# SoundDetectorModule.net
KiCad netlist of a schematic drawn in EAGLE
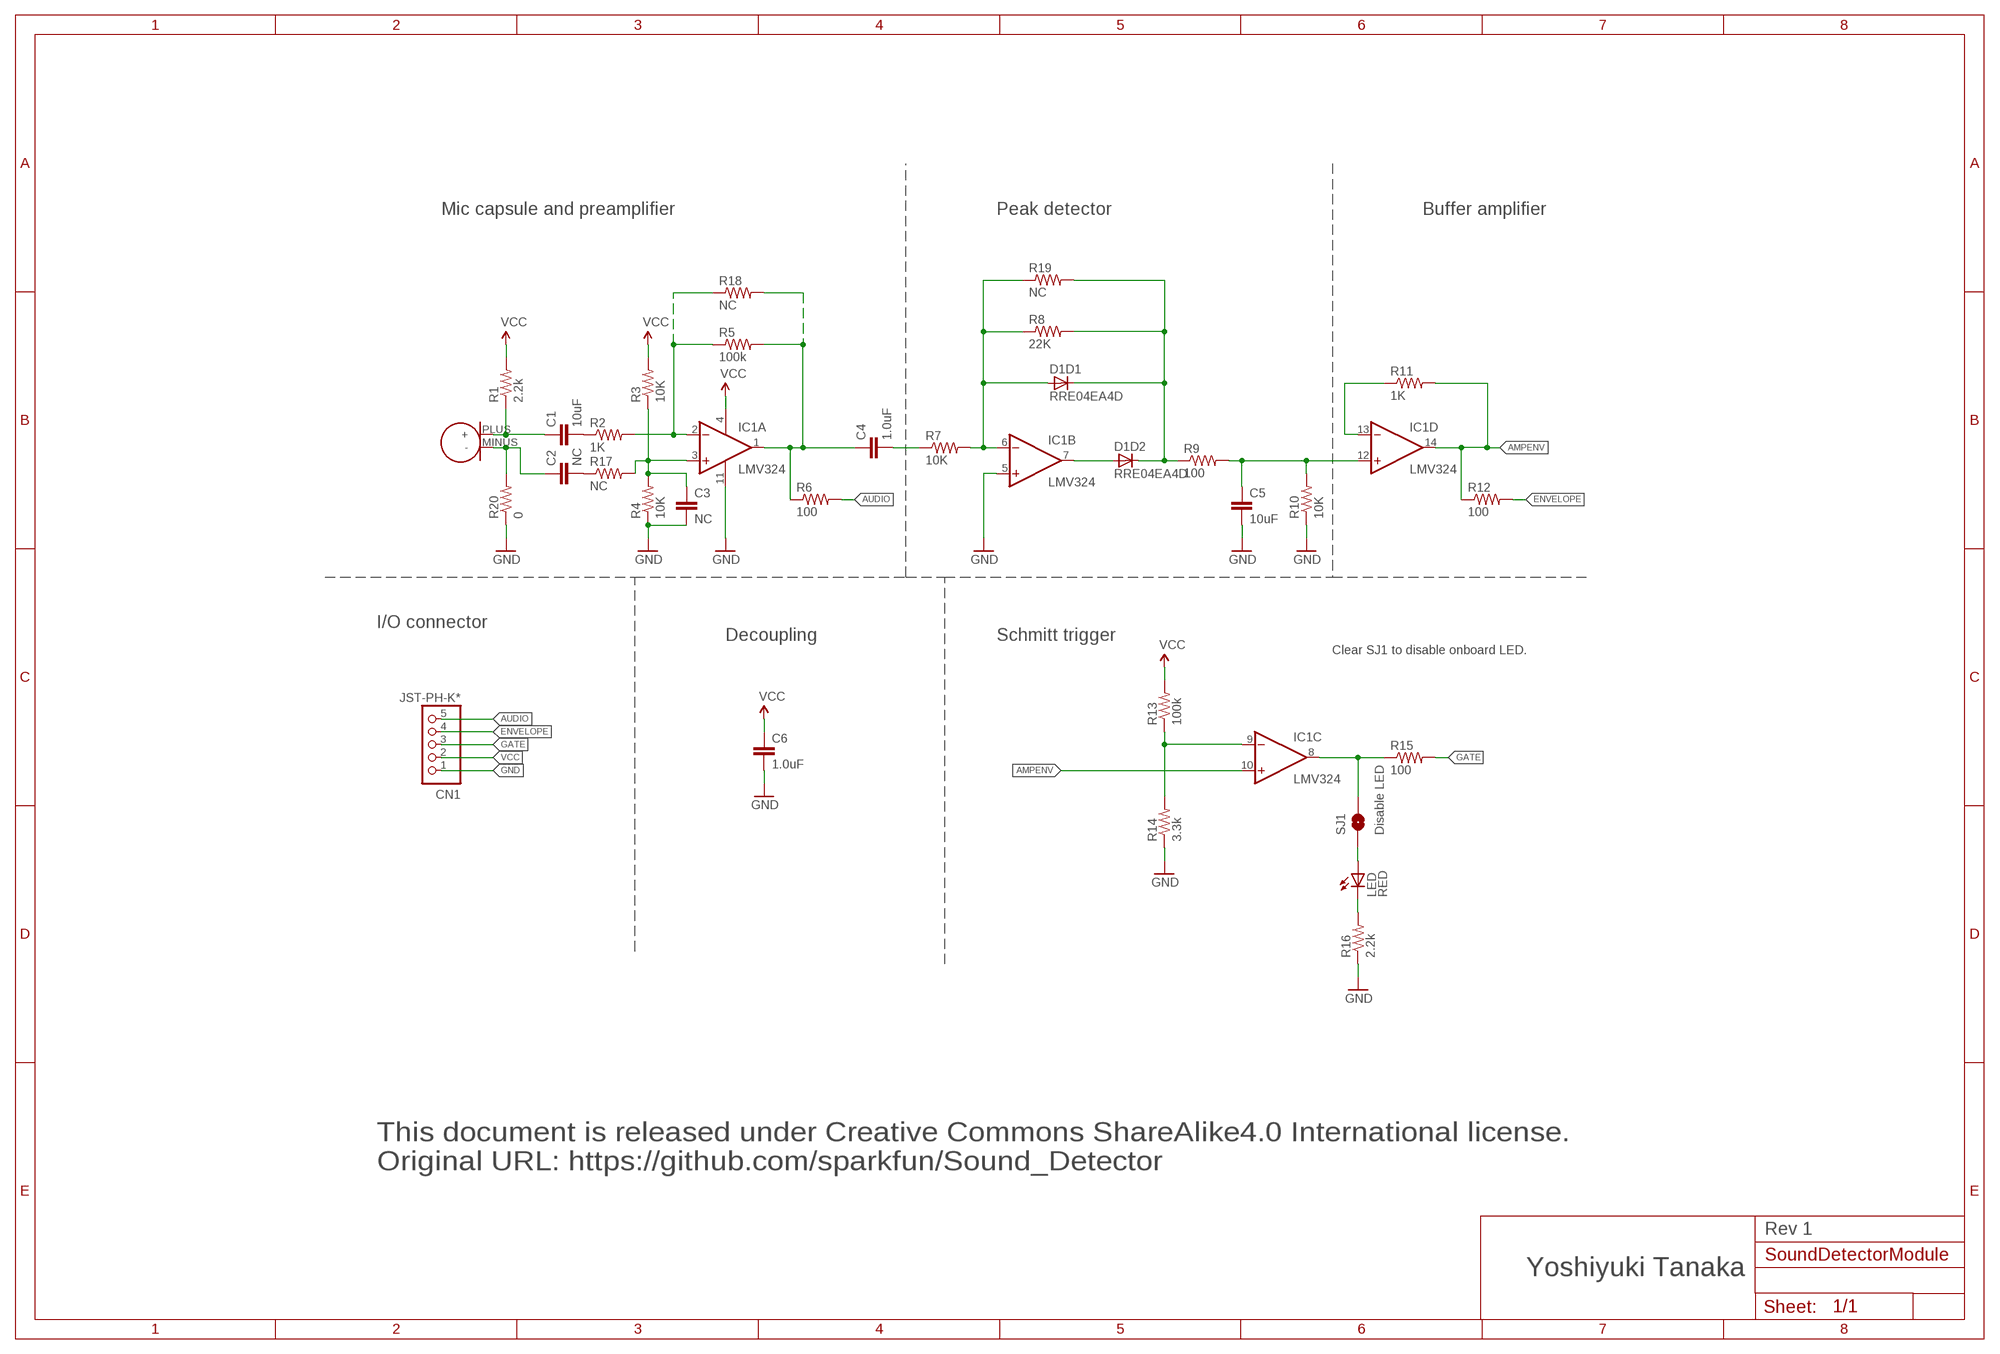
[diagram p0: schematic, sheet 1]

(export (version "E")
  (design (tool "Eeschema 10.0.6"))
  (components
    (comp (ref "A1")
      (value "MO093803-3")
      (footprint "eagle-import:MO093803-3")
      (libsource (lib "eagle-import") (part "MO093803-3"))
    )
    (comp (ref "C1")
      (value "10uF")
      (footprint "eagle-import:C1206")
      (libsource (lib "eagle-import") (part "C-EUC1206"))
    )
    (comp (ref "C2")
      (value "NC")
      (footprint "eagle-import:C0603")
      (libsource (lib "eagle-import") (part "C-EUC0603"))
    )
    (comp (ref "C3")
      (value "NC")
      (footprint "eagle-import:C0603")
      (libsource (lib "eagle-import") (part "C-EUC0603"))
    )
    (comp (ref "C4")
      (value "1.0uF")
      (footprint "eagle-import:C0603")
      (libsource (lib "eagle-import") (part "C-EUC0603"))
    )
    (comp (ref "C5")
      (value "10uF")
      (footprint "eagle-import:C1206")
      (libsource (lib "eagle-import") (part "C-EUC1206"))
    )
    (comp (ref "C6")
      (value "1.0uF")
      (footprint "eagle-import:C0603")
      (libsource (lib "eagle-import") (part "C-EUC0603"))
    )
    (comp (ref "CN1")
      (value "JST-PH-K*")
      (footprint "eagle-import:B5B-PH-SM4-TB")
      (libsource (lib "eagle-import") (part "B5B-PH-SM4-TB"))
    )
    (comp (ref "D1")
      (value "RRE04EA4D")
      (footprint "eagle-import:TSMD5")
      (libsource (lib "eagle-import") (part "RRE04EA4D"))
    )
    (comp (ref "IC1")
      (value "LMV324")
      (footprint "eagle-import:SO14")
      (libsource (lib "eagle-import") (part "LMV324"))
    )
    (comp (ref "LED")
      (value "RED")
      (footprint "eagle-import:SML-E1X")
      (libsource (lib "eagle-import") (part "SML-E1X"))
    )
    (comp (ref "R1")
      (value "2.2k")
      (footprint "eagle-import:R0603")
      (libsource (lib "eagle-import") (part "R-US_R0603"))
    )
    (comp (ref "R2")
      (value "1K")
      (footprint "eagle-import:R0603")
      (libsource (lib "eagle-import") (part "R-US_R0603"))
    )
    (comp (ref "R3")
      (value "10K")
      (footprint "eagle-import:R0603")
      (libsource (lib "eagle-import") (part "R-US_R0603"))
    )
    (comp (ref "R4")
      (value "10K")
      (footprint "eagle-import:R0603")
      (libsource (lib "eagle-import") (part "R-US_R0603"))
    )
    (comp (ref "R5")
      (value "100k")
      (footprint "eagle-import:R0603")
      (libsource (lib "eagle-import") (part "R-US_R0603"))
    )
    (comp (ref "R6")
      (value "100")
      (footprint "eagle-import:R0603")
      (libsource (lib "eagle-import") (part "R-US_R0603"))
    )
    (comp (ref "R7")
      (value "10K")
      (footprint "eagle-import:R0603")
      (libsource (lib "eagle-import") (part "R-US_R0603"))
    )
    (comp (ref "R8")
      (value "22K")
      (footprint "eagle-import:R0603")
      (libsource (lib "eagle-import") (part "R-US_R0603"))
    )
    (comp (ref "R9")
      (value "100")
      (footprint "eagle-import:R0603")
      (libsource (lib "eagle-import") (part "R-US_R0603"))
    )
    (comp (ref "R10")
      (value "10K")
      (footprint "eagle-import:R0603")
      (libsource (lib "eagle-import") (part "R-US_R0603"))
    )
    (comp (ref "R11")
      (value "1K")
      (footprint "eagle-import:R0603")
      (libsource (lib "eagle-import") (part "R-US_R0603"))
    )
    (comp (ref "R12")
      (value "100")
      (footprint "eagle-import:R0603")
      (libsource (lib "eagle-import") (part "R-US_R0603"))
    )
    (comp (ref "R13")
      (value "100k")
      (footprint "eagle-import:R0603")
      (libsource (lib "eagle-import") (part "R-US_R0603"))
    )
    (comp (ref "R14")
      (value "3.3k")
      (footprint "eagle-import:R0603")
      (libsource (lib "eagle-import") (part "R-US_R0603"))
    )
    (comp (ref "R15")
      (value "100")
      (footprint "eagle-import:R0603")
      (libsource (lib "eagle-import") (part "R-US_R0603"))
    )
    (comp (ref "R16")
      (value "2.2k")
      (footprint "eagle-import:R0603")
      (libsource (lib "eagle-import") (part "R-US_R0603"))
    )
    (comp (ref "R17")
      (value "NC")
      (footprint "eagle-import:R0603")
      (libsource (lib "eagle-import") (part "R-US_R0603"))
    )
    (comp (ref "R18")
      (value "NC")
      (footprint "eagle-import:0207_7")
      (libsource (lib "eagle-import") (part "resistor_R-US_0207/7"))
    )
    (comp (ref "R19")
      (value "NC")
      (footprint "eagle-import:0207_7")
      (libsource (lib "eagle-import") (part "resistor_R-US_0207/7"))
    )
    (comp (ref "R20")
      (value "0")
      (footprint "eagle-import:R0603")
      (libsource (lib "eagle-import") (part "R-US_R0603"))
    )
    (comp (ref "SJ1")
      (value "Disable LED")
      (footprint "eagle-import:SJ_2S")
      (libsource (lib "eagle-import") (part "SOLDERJUMPERNC"))
    )
  )
  (nets
    (net (code "1") (name "AMPENV") (class "Default")
      (node (ref "IC1") (pin "10") (pinfunction "+IN_10") (pintype "input"))
      (node (ref "IC1") (pin "14") (pinfunction "OUT_14") (pintype "output"))
      (node (ref "R11") (pin "2") (pinfunction "2_2") (pintype "passive"))
      (node (ref "R12") (pin "1") (pinfunction "1_1") (pintype "passive"))
    )
    (net (code "2") (name "AUDIO") (class "Default")
      (node (ref "CN1") (pin "5") (pinfunction "5_5") (pintype "passive"))
      (node (ref "R6") (pin "2") (pinfunction "2_2") (pintype "passive"))
    )
    (net (code "3") (name "ENVELOPE") (class "Default")
      (node (ref "CN1") (pin "4") (pinfunction "4_4") (pintype "passive"))
      (node (ref "R12") (pin "2") (pinfunction "2_2") (pintype "passive"))
    )
    (net (code "4") (name "GATE") (class "Default")
      (node (ref "CN1") (pin "3") (pinfunction "3_3") (pintype "passive"))
      (node (ref "R15") (pin "2") (pinfunction "2_2") (pintype "passive"))
    )
    (net (code "5") (name "GND") (class "Default")
      (node (ref "C3") (pin "2") (pinfunction "2_2") (pintype "passive"))
      (node (ref "C5") (pin "2") (pinfunction "2_2") (pintype "passive"))
      (node (ref "C6") (pin "2") (pinfunction "2_2") (pintype "passive"))
      (node (ref "CN1") (pin "1") (pinfunction "1_1") (pintype "passive"))
      (node (ref "IC1") (pin "11") (pinfunction "V-_11") (pintype "power_in"))
      (node (ref "IC1") (pin "5") (pinfunction "+IN_5") (pintype "input"))
      (node (ref "R10") (pin "1") (pinfunction "1_1") (pintype "passive"))
      (node (ref "R14") (pin "1") (pinfunction "1_1") (pintype "passive"))
      (node (ref "R16") (pin "1") (pinfunction "1_1") (pintype "passive"))
      (node (ref "R20") (pin "1") (pinfunction "1_1") (pintype "passive"))
      (node (ref "R4") (pin "1") (pinfunction "1_1") (pintype "passive"))
    )
    (net (code "6") (name "Net-(A1-+)") (class "Default")
      (node (ref "A1") (pin "PLUS") (pinfunction "+_PLUS") (pintype "bidirectional"))
      (node (ref "C1") (pin "1") (pinfunction "1_1") (pintype "passive"))
      (node (ref "R1") (pin "1") (pinfunction "1_1") (pintype "passive"))
    )
    (net (code "7") (name "Net-(A1--)") (class "Default")
      (node (ref "A1") (pin "MINUS") (pinfunction "-_MINUS") (pintype "bidirectional"))
      (node (ref "C2") (pin "1") (pinfunction "1_1") (pintype "passive"))
      (node (ref "R20") (pin "2") (pinfunction "2_2") (pintype "passive"))
    )
    (net (code "8") (name "Net-(C1-Pad2)") (class "Default")
      (node (ref "C1") (pin "2") (pinfunction "2_2") (pintype "passive"))
      (node (ref "R2") (pin "1") (pinfunction "1_1") (pintype "passive"))
    )
    (net (code "9") (name "Net-(C2-Pad2)") (class "Default")
      (node (ref "C2") (pin "2") (pinfunction "2_2") (pintype "passive"))
      (node (ref "R17") (pin "1") (pinfunction "1_1") (pintype "passive"))
    )
    (net (code "10") (name "Net-(C4-Pad2)") (class "Default")
      (node (ref "C4") (pin "2") (pinfunction "2_2") (pintype "passive"))
      (node (ref "R7") (pin "1") (pinfunction "1_1") (pintype "passive"))
    )
    (net (code "11") (name "Net-(D1A-A)") (class "Default")
      (node (ref "D1") (pin "1") (pinfunction "A_1") (pintype "passive"))
      (node (ref "IC1") (pin "6") (pinfunction "-IN_6") (pintype "input"))
      (node (ref "R19") (pin "1") (pinfunction "1_1") (pintype "passive"))
      (node (ref "R7") (pin "2") (pinfunction "2_2") (pintype "passive"))
      (node (ref "R8") (pin "1") (pinfunction "1_1") (pintype "passive"))
    )
    (net (code "12") (name "Net-(D1A-C)") (class "Default")
      (node (ref "D1") (pin "4") (pinfunction "C_4") (pintype "passive"))
      (node (ref "D1") (pin "5") (pinfunction "C_5") (pintype "passive"))
      (node (ref "R19") (pin "2") (pinfunction "2_2") (pintype "passive"))
      (node (ref "R8") (pin "2") (pinfunction "2_2") (pintype "passive"))
      (node (ref "R9") (pin "1") (pinfunction "1_1") (pintype "passive"))
    )
    (net (code "13") (name "Net-(D1B-A)") (class "Default")
      (node (ref "D1") (pin "3") (pinfunction "A_3") (pintype "passive"))
      (node (ref "IC1") (pin "7") (pinfunction "OUT_7") (pintype "output"))
    )
    (net (code "14") (name "Net-(IC1A-+IN)") (class "Default")
      (node (ref "C3") (pin "1") (pinfunction "1_1") (pintype "passive"))
      (node (ref "IC1") (pin "3") (pinfunction "+IN_3") (pintype "input"))
      (node (ref "R17") (pin "2") (pinfunction "2_2") (pintype "passive"))
      (node (ref "R3") (pin "1") (pinfunction "1_1") (pintype "passive"))
      (node (ref "R4") (pin "2") (pinfunction "2_2") (pintype "passive"))
    )
    (net (code "15") (name "Net-(IC1A--IN)") (class "Default")
      (node (ref "IC1") (pin "2") (pinfunction "-IN_2") (pintype "input"))
      (node (ref "R18") (pin "1") (pinfunction "1_1") (pintype "passive"))
      (node (ref "R2") (pin "2") (pinfunction "2_2") (pintype "passive"))
      (node (ref "R5") (pin "1") (pinfunction "1_1") (pintype "passive"))
    )
    (net (code "16") (name "Net-(IC1A-OUT)") (class "Default")
      (node (ref "C4") (pin "1") (pinfunction "1_1") (pintype "passive"))
      (node (ref "IC1") (pin "1") (pinfunction "OUT_1") (pintype "output"))
      (node (ref "R18") (pin "2") (pinfunction "2_2") (pintype "passive"))
      (node (ref "R5") (pin "2") (pinfunction "2_2") (pintype "passive"))
      (node (ref "R6") (pin "1") (pinfunction "1_1") (pintype "passive"))
    )
    (net (code "17") (name "Net-(IC1C--IN)") (class "Default")
      (node (ref "IC1") (pin "9") (pinfunction "-IN_9") (pintype "input"))
      (node (ref "R13") (pin "1") (pinfunction "1_1") (pintype "passive"))
      (node (ref "R14") (pin "2") (pinfunction "2_2") (pintype "passive"))
    )
    (net (code "18") (name "Net-(IC1C-OUT)") (class "Default")
      (node (ref "IC1") (pin "8") (pinfunction "OUT_8") (pintype "output"))
      (node (ref "R15") (pin "1") (pinfunction "1_1") (pintype "passive"))
      (node (ref "SJ1") (pin "2") (pinfunction "2_2") (pintype "passive"))
    )
    (net (code "19") (name "Net-(IC1D-+IN)") (class "Default")
      (node (ref "C5") (pin "1") (pinfunction "1_1") (pintype "passive"))
      (node (ref "IC1") (pin "12") (pinfunction "+IN_12") (pintype "input"))
      (node (ref "R10") (pin "2") (pinfunction "2_2") (pintype "passive"))
      (node (ref "R9") (pin "2") (pinfunction "2_2") (pintype "passive"))
    )
    (net (code "20") (name "Net-(IC1D--IN)") (class "Default")
      (node (ref "IC1") (pin "13") (pinfunction "-IN_13") (pintype "input"))
      (node (ref "R11") (pin "1") (pinfunction "1_1") (pintype "passive"))
    )
    (net (code "21") (name "Net-(LED-PadA)") (class "Default")
      (node (ref "LED") (pin "A") (pinfunction "A_A") (pintype "passive"))
      (node (ref "SJ1") (pin "1") (pinfunction "1_1") (pintype "passive"))
    )
    (net (code "22") (name "Net-(LED-PadC)") (class "Default")
      (node (ref "LED") (pin "C") (pinfunction "C_C") (pintype "passive"))
      (node (ref "R16") (pin "2") (pinfunction "2_2") (pintype "passive"))
    )
    (net (code "23") (name "VCC") (class "Default")
      (node (ref "C6") (pin "1") (pinfunction "1_1") (pintype "passive"))
      (node (ref "CN1") (pin "2") (pinfunction "2_2") (pintype "passive"))
      (node (ref "IC1") (pin "4") (pinfunction "V+_4") (pintype "power_in"))
      (node (ref "R1") (pin "2") (pinfunction "2_2") (pintype "passive"))
      (node (ref "R13") (pin "2") (pinfunction "2_2") (pintype "passive"))
      (node (ref "R3") (pin "2") (pinfunction "2_2") (pintype "passive"))
    )
  )
)
